# Sheet1.net
KiCad netlist of a schematic drawn in Altium Designer
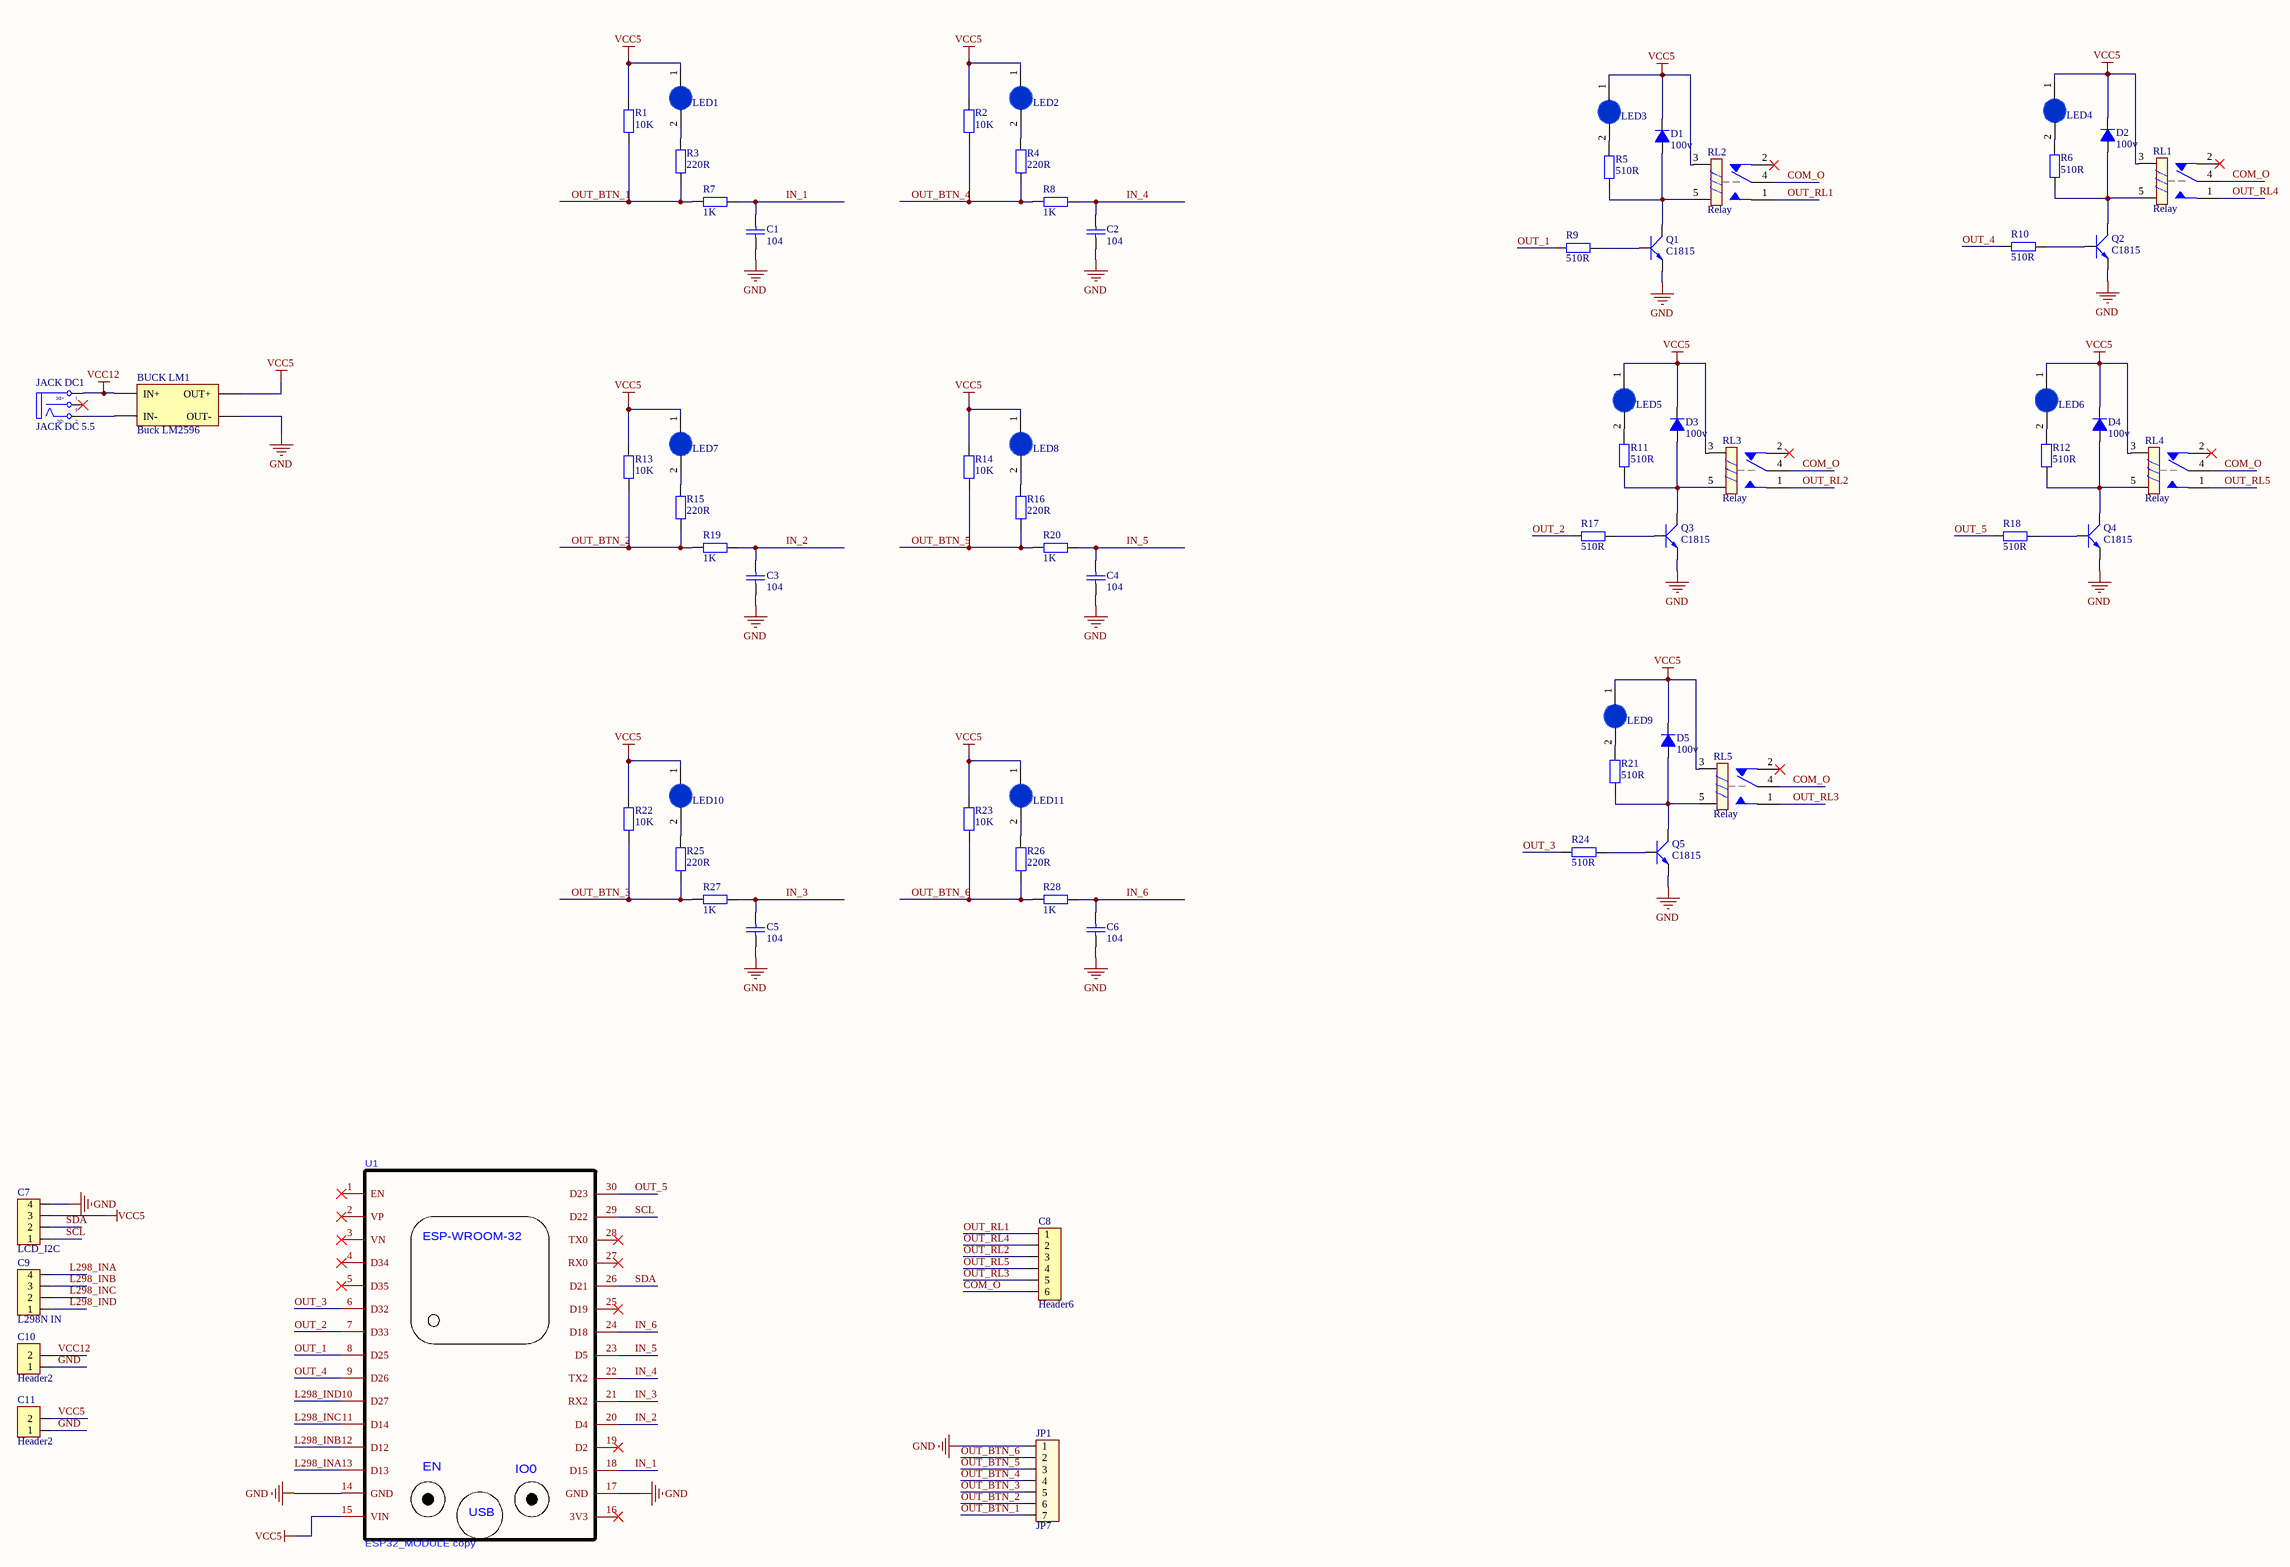
[diagram p0: Sheet1.SchDoc]

(export (version "E")
  (design (tool "Eeschema 10.0.6"))
  (components
    (comp (ref "BUCK LM1")
      (value "Buck LM2596")
      (footprint "BUCK LM2596")
      (libsource (lib "myLib_v1") (part "Buck LM2596"))
    )
    (comp (ref "C1")
      (value "104")
      (footprint "tu gom")
      (description "Cắm")
      (libsource (lib "Altium_Lib_by_KhueNguyenCreator") (part "Tu gom 104 50V"))
    )
    (comp (ref "C2")
      (value "104")
      (footprint "tu gom")
      (description "Cắm")
      (libsource (lib "Altium_Lib_by_KhueNguyenCreator") (part "Tu gom 104 50V"))
    )
    (comp (ref "C3")
      (value "104")
      (footprint "tu gom")
      (description "Cắm")
      (libsource (lib "Altium_Lib_by_KhueNguyenCreator") (part "Tu gom 104 50V"))
    )
    (comp (ref "C4")
      (value "104")
      (footprint "tu gom")
      (description "Cắm")
      (libsource (lib "Altium_Lib_by_KhueNguyenCreator") (part "Tu gom 104 50V"))
    )
    (comp (ref "C5")
      (value "104")
      (footprint "tu gom")
      (description "Cắm")
      (libsource (lib "Altium_Lib_by_KhueNguyenCreator") (part "Tu gom 104 50V"))
    )
    (comp (ref "C6")
      (value "104")
      (footprint "tu gom")
      (description "Cắm")
      (libsource (lib "Altium_Lib_by_KhueNguyenCreator") (part "Tu gom 104 50V"))
    )
    (comp (ref "C7")
      (value "LCD_I2C")
      (footprint "Header4")
      (description "Header IDC, 4 x 1 Pin Vertical 2.54mm Pitch (Non-Boxed, Male)")
      (fields
        (field (name "MANUFACTURER") "Würth Elektronik eiSos GmbH")
        (field (name "PARTNO") "613002143121")
        (field (name "CREATED BY") "Karrer Zheng")
      )
      (libsource (lib "myLib_v1") (part "Header4"))
    )
    (comp (ref "C8")
      (value "Header6")
      (footprint "Header6")
      (description "Header IDC, 6 x 1 Pin Vertical 2.54mm Pitch (Non-Boxed, Male)")
      (fields
        (field (name "MANUFACTURER") "Würth Elektronik eiSos GmbH")
        (field (name "PARTNO") "613002143121")
        (field (name "CREATED BY") "Karrer Zheng")
      )
      (libsource (lib "myLib_v1") (part "Header6"))
    )
    (comp (ref "C9")
      (value "L298N IN")
      (footprint "Header4")
      (description "Header IDC, 4 x 1 Pin Vertical 2.54mm Pitch (Non-Boxed, Male)")
      (fields
        (field (name "MANUFACTURER") "Würth Elektronik eiSos GmbH")
        (field (name "PARTNO") "613002143121")
        (field (name "CREATED BY") "Karrer Zheng")
      )
      (libsource (lib "myLib_v1") (part "Header4"))
    )
    (comp (ref "C10")
      (value "Header2")
      (footprint "Header2")
      (description "Header IDC, 2 x 1 Pin Vertical 2.54mm Pitch (Non-Boxed, Male)")
      (fields
        (field (name "MANUFACTURER") "Würth Elektronik eiSos GmbH")
        (field (name "PARTNO") "613002143121")
        (field (name "CREATED BY") "Karrer Zheng")
      )
      (libsource (lib "myLib_v1") (part "Header2"))
    )
    (comp (ref "C11")
      (value "Header2")
      (footprint "Header2")
      (description "Header IDC, 2 x 1 Pin Vertical 2.54mm Pitch (Non-Boxed, Male)")
      (fields
        (field (name "MANUFACTURER") "Würth Elektronik eiSos GmbH")
        (field (name "PARTNO") "613002143121")
        (field (name "CREATED BY") "Karrer Zheng")
      )
      (libsource (lib "myLib_v1") (part "Header2"))
    )
    (comp (ref "D1")
      (value "100v")
      (footprint "DIODE 0.5A")
      (description "Cắm")
      (libsource (lib "Altium_Lib_by_KhueNguyenCreator") (part "Diode 1N4148"))
    )
    (comp (ref "D2")
      (value "100v")
      (footprint "DIODE 0.5A")
      (description "Cắm")
      (libsource (lib "Altium_Lib_by_KhueNguyenCreator") (part "Diode 1N4148"))
    )
    (comp (ref "D3")
      (value "100v")
      (footprint "DIODE 0.5A")
      (description "Cắm")
      (libsource (lib "Altium_Lib_by_KhueNguyenCreator") (part "Diode 1N4148"))
    )
    (comp (ref "D4")
      (value "100v")
      (footprint "DIODE 0.5A")
      (description "Cắm")
      (libsource (lib "Altium_Lib_by_KhueNguyenCreator") (part "Diode 1N4148"))
    )
    (comp (ref "D5")
      (value "100v")
      (footprint "DIODE 0.5A")
      (description "Cắm")
      (libsource (lib "Altium_Lib_by_KhueNguyenCreator") (part "Diode 1N4148"))
    )
    (comp (ref "JACK DC1")
      (value "JACK DC 5.5")
      (footprint "JACK DC 5.5")
      (libsource (lib "Altium_Lib_by_KhueNguyenCreator") (part "JACK DC 5.5"))
    )
    (comp (ref "JP1")
      (value "JP7")
      (footprint "Header7")
      (description "Connector 7")
      (libsource (lib "myLib_v1") (part "Header7"))
    )
    (comp (ref "LED1")
      (value "LED 3mm")
      (footprint "LED-3MM-BLUE")
      (description "Cắm")
      (libsource (lib "myLib_v1") (part "LED 3mm Xanh Duong"))
    )
    (comp (ref "LED2")
      (value "LED 3mm")
      (footprint "LED-3MM-BLUE")
      (description "Cắm")
      (libsource (lib "myLib_v1") (part "LED 3mm Xanh Duong"))
    )
    (comp (ref "LED3")
      (value "LED 3mm")
      (footprint "LED-3MM-BLUE")
      (description "Cắm")
      (libsource (lib "myLib_v1") (part "LED 3mm Xanh Duong"))
    )
    (comp (ref "LED4")
      (value "LED 3mm")
      (footprint "LED-3MM-BLUE")
      (description "Cắm")
      (libsource (lib "myLib_v1") (part "LED 3mm Xanh Duong"))
    )
    (comp (ref "LED5")
      (value "LED 3mm")
      (footprint "LED-3MM-BLUE")
      (description "Cắm")
      (libsource (lib "myLib_v1") (part "LED 3mm Xanh Duong"))
    )
    (comp (ref "LED6")
      (value "LED 3mm")
      (footprint "LED-3MM-BLUE")
      (description "Cắm")
      (libsource (lib "myLib_v1") (part "LED 3mm Xanh Duong"))
    )
    (comp (ref "LED7")
      (value "LED 3mm")
      (footprint "LED-3MM-BLUE")
      (description "Cắm")
      (libsource (lib "myLib_v1") (part "LED 3mm Xanh Duong"))
    )
    (comp (ref "LED8")
      (value "LED 3mm")
      (footprint "LED-3MM-BLUE")
      (description "Cắm")
      (libsource (lib "myLib_v1") (part "LED 3mm Xanh Duong"))
    )
    (comp (ref "LED9")
      (value "LED 3mm")
      (footprint "LED-3MM-BLUE")
      (description "Cắm")
      (libsource (lib "myLib_v1") (part "LED 3mm Xanh Duong"))
    )
    (comp (ref "LED10")
      (value "LED 3mm")
      (footprint "LED-3MM-BLUE")
      (description "Cắm")
      (libsource (lib "myLib_v1") (part "LED 3mm Xanh Duong"))
    )
    (comp (ref "LED11")
      (value "LED 3mm")
      (footprint "LED-3MM-BLUE")
      (description "Cắm")
      (libsource (lib "myLib_v1") (part "LED 3mm Xanh Duong"))
    )
    (comp (ref "Q1")
      (value "C1815")
      (footprint "C1815_cam")
      (description "NPN 600mW, ECB")
      (libsource (lib "myLib_v1") (part "C1815"))
    )
    (comp (ref "Q2")
      (value "C1815")
      (footprint "C1815_cam")
      (description "NPN 600mW, ECB")
      (libsource (lib "myLib_v1") (part "C1815"))
    )
    (comp (ref "Q3")
      (value "C1815")
      (footprint "C1815_cam")
      (description "NPN 600mW, ECB")
      (libsource (lib "myLib_v1") (part "C1815"))
    )
    (comp (ref "Q4")
      (value "C1815")
      (footprint "C1815_cam")
      (description "NPN 600mW, ECB")
      (libsource (lib "myLib_v1") (part "C1815"))
    )
    (comp (ref "Q5")
      (value "C1815")
      (footprint "C1815_cam")
      (description "NPN 600mW, ECB")
      (libsource (lib "myLib_v1") (part "C1815"))
    )
    (comp (ref "R1")
      (value "10K")
      (footprint "R1/4W")
      (description "Resistor 1/4W")
      (libsource (lib "myLib_v1") (part "R1/4W"))
    )
    (comp (ref "R2")
      (value "10K")
      (footprint "R1/4W")
      (description "Resistor 1/4W")
      (libsource (lib "myLib_v1") (part "R1/4W"))
    )
    (comp (ref "R3")
      (value "220R")
      (footprint "R1/4W")
      (description "Resistor 1/4W")
      (libsource (lib "myLib_v1") (part "R1/4W"))
    )
    (comp (ref "R4")
      (value "220R")
      (footprint "R1/4W")
      (description "Resistor 1/4W")
      (libsource (lib "myLib_v1") (part "R1/4W"))
    )
    (comp (ref "R5")
      (value "510R")
      (footprint "R1/4W")
      (description "Resistor 1/4W")
      (libsource (lib "myLib_v1") (part "R1/4W"))
    )
    (comp (ref "R6")
      (value "510R")
      (footprint "R1/4W")
      (description "Resistor 1/4W")
      (libsource (lib "myLib_v1") (part "R1/4W"))
    )
    (comp (ref "R7")
      (value "1K")
      (footprint "R1/4W")
      (description "Resistor 1/4W")
      (libsource (lib "myLib_v1") (part "R1/4W"))
    )
    (comp (ref "R8")
      (value "1K")
      (footprint "R1/4W")
      (description "Resistor 1/4W")
      (libsource (lib "myLib_v1") (part "R1/4W"))
    )
    (comp (ref "R9")
      (value "510R")
      (footprint "R1/4W")
      (description "Resistor 1/4W")
      (libsource (lib "myLib_v1") (part "R1/4W"))
    )
    (comp (ref "R10")
      (value "510R")
      (footprint "R1/4W")
      (description "Resistor 1/4W")
      (libsource (lib "myLib_v1") (part "R1/4W"))
    )
    (comp (ref "R11")
      (value "510R")
      (footprint "R1/4W")
      (description "Resistor 1/4W")
      (libsource (lib "myLib_v1") (part "R1/4W"))
    )
    (comp (ref "R12")
      (value "510R")
      (footprint "R1/4W")
      (description "Resistor 1/4W")
      (libsource (lib "myLib_v1") (part "R1/4W"))
    )
    (comp (ref "R13")
      (value "10K")
      (footprint "R1/4W")
      (description "Resistor 1/4W")
      (libsource (lib "myLib_v1") (part "R1/4W"))
    )
    (comp (ref "R14")
      (value "10K")
      (footprint "R1/4W")
      (description "Resistor 1/4W")
      (libsource (lib "myLib_v1") (part "R1/4W"))
    )
    (comp (ref "R15")
      (value "220R")
      (footprint "R1/4W")
      (description "Resistor 1/4W")
      (libsource (lib "myLib_v1") (part "R1/4W"))
    )
    (comp (ref "R16")
      (value "220R")
      (footprint "R1/4W")
      (description "Resistor 1/4W")
      (libsource (lib "myLib_v1") (part "R1/4W"))
    )
    (comp (ref "R17")
      (value "510R")
      (footprint "R1/4W")
      (description "Resistor 1/4W")
      (libsource (lib "myLib_v1") (part "R1/4W"))
    )
    (comp (ref "R18")
      (value "510R")
      (footprint "R1/4W")
      (description "Resistor 1/4W")
      (libsource (lib "myLib_v1") (part "R1/4W"))
    )
    (comp (ref "R19")
      (value "1K")
      (footprint "R1/4W")
      (description "Resistor 1/4W")
      (libsource (lib "myLib_v1") (part "R1/4W"))
    )
    (comp (ref "R20")
      (value "1K")
      (footprint "R1/4W")
      (description "Resistor 1/4W")
      (libsource (lib "myLib_v1") (part "R1/4W"))
    )
    (comp (ref "R21")
      (value "510R")
      (footprint "R1/4W")
      (description "Resistor 1/4W")
      (libsource (lib "myLib_v1") (part "R1/4W"))
    )
    (comp (ref "R22")
      (value "10K")
      (footprint "R1/4W")
      (description "Resistor 1/4W")
      (libsource (lib "myLib_v1") (part "R1/4W"))
    )
    (comp (ref "R23")
      (value "10K")
      (footprint "R1/4W")
      (description "Resistor 1/4W")
      (libsource (lib "myLib_v1") (part "R1/4W"))
    )
    (comp (ref "R24")
      (value "510R")
      (footprint "R1/4W")
      (description "Resistor 1/4W")
      (libsource (lib "myLib_v1") (part "R1/4W"))
    )
    (comp (ref "R25")
      (value "220R")
      (footprint "R1/4W")
      (description "Resistor 1/4W")
      (libsource (lib "myLib_v1") (part "R1/4W"))
    )
    (comp (ref "R26")
      (value "220R")
      (footprint "R1/4W")
      (description "Resistor 1/4W")
      (libsource (lib "myLib_v1") (part "R1/4W"))
    )
    (comp (ref "R27")
      (value "1K")
      (footprint "R1/4W")
      (description "Resistor 1/4W")
      (libsource (lib "myLib_v1") (part "R1/4W"))
    )
    (comp (ref "R28")
      (value "1K")
      (footprint "R1/4W")
      (description "Resistor 1/4W")
      (libsource (lib "myLib_v1") (part "R1/4W"))
    )
    (comp (ref "RL1")
      (value "Relay")
      (footprint "RELAY_SRA_05VDC_SL_C")
      (description "Relay 5 Chan")
      (libsource (lib "myLib_v1") (part "RL_SRA-05VDC-SL-C"))
    )
    (comp (ref "RL2")
      (value "Relay")
      (footprint "RELAY_SRA_05VDC_SL_C")
      (description "Relay 5 Chan")
      (libsource (lib "myLib_v1") (part "RL_SRA-05VDC-SL-C"))
    )
    (comp (ref "RL3")
      (value "Relay")
      (footprint "RELAY_SRA_05VDC_SL_C")
      (description "Relay 5 Chan")
      (libsource (lib "myLib_v1") (part "RL_SRA-05VDC-SL-C"))
    )
    (comp (ref "RL4")
      (value "Relay")
      (footprint "RELAY_SRA_05VDC_SL_C")
      (description "Relay 5 Chan")
      (libsource (lib "myLib_v1") (part "RL_SRA-05VDC-SL-C"))
    )
    (comp (ref "RL5")
      (value "Relay")
      (footprint "RELAY_SRA_05VDC_SL_C")
      (description "Relay 5 Chan")
      (libsource (lib "myLib_v1") (part "RL_SRA-05VDC-SL-C"))
    )
    (comp (ref "U1")
      (value "ESP32_MODULE copy")
      (footprint "ESP32-WIFIMODULE-FOOTPRINT")
      (libsource (lib "myLib_v1") (part "ESP32_MODULE copy"))
    )
  )
  (nets
    (net (code "1") (name "/COM_O") (class "Default")
      (node (ref "C8") (pin "6") (pinfunction "6_6") (pintype "passive"))
      (node (ref "RL1") (pin "4") (pinfunction "4_4") (pintype "passive"))
      (node (ref "RL2") (pin "4") (pinfunction "4_4") (pintype "passive"))
      (node (ref "RL3") (pin "4") (pinfunction "4_4") (pintype "passive"))
      (node (ref "RL4") (pin "4") (pinfunction "4_4") (pintype "passive"))
      (node (ref "RL5") (pin "4") (pinfunction "4_4") (pintype "passive"))
    )
    (net (code "2") (name "/IN_1") (class "Default")
      (node (ref "C1") (pin "1") (pinfunction "1_1") (pintype "passive"))
      (node (ref "R7") (pin "1") (pinfunction "1_1") (pintype "passive"))
      (node (ref "U1") (pin "18") (pinfunction "D15_18") (pintype "passive"))
    )
    (net (code "3") (name "/IN_2") (class "Default")
      (node (ref "C3") (pin "1") (pinfunction "1_1") (pintype "passive"))
      (node (ref "R19") (pin "1") (pinfunction "1_1") (pintype "passive"))
      (node (ref "U1") (pin "20") (pinfunction "D4_20") (pintype "passive"))
    )
    (net (code "4") (name "/IN_3") (class "Default")
      (node (ref "C5") (pin "1") (pinfunction "1_1") (pintype "passive"))
      (node (ref "R27") (pin "1") (pinfunction "1_1") (pintype "passive"))
      (node (ref "U1") (pin "21") (pinfunction "RX2_21") (pintype "passive"))
    )
    (net (code "5") (name "/IN_4") (class "Default")
      (node (ref "C2") (pin "1") (pinfunction "1_1") (pintype "passive"))
      (node (ref "R8") (pin "1") (pinfunction "1_1") (pintype "passive"))
      (node (ref "U1") (pin "22") (pinfunction "TX2_22") (pintype "passive"))
    )
    (net (code "6") (name "/IN_5") (class "Default")
      (node (ref "C4") (pin "1") (pinfunction "1_1") (pintype "passive"))
      (node (ref "R20") (pin "1") (pinfunction "1_1") (pintype "passive"))
      (node (ref "U1") (pin "23") (pinfunction "D5_23") (pintype "passive"))
    )
    (net (code "7") (name "/IN_6") (class "Default")
      (node (ref "C6") (pin "1") (pinfunction "1_1") (pintype "passive"))
      (node (ref "R28") (pin "1") (pinfunction "1_1") (pintype "passive"))
      (node (ref "U1") (pin "24") (pinfunction "D18_24") (pintype "passive"))
    )
    (net (code "8") (name "/L298_INA") (class "Default")
      (node (ref "C9") (pin "4") (pinfunction "4_4") (pintype "passive"))
      (node (ref "U1") (pin "13") (pinfunction "D13_13") (pintype "passive"))
    )
    (net (code "9") (name "/L298_INB") (class "Default")
      (node (ref "C9") (pin "3") (pinfunction "3_3") (pintype "passive"))
      (node (ref "U1") (pin "12") (pinfunction "D12_12") (pintype "passive"))
    )
    (net (code "10") (name "/L298_INC") (class "Default")
      (node (ref "C9") (pin "2") (pinfunction "2_2") (pintype "passive"))
      (node (ref "U1") (pin "11") (pinfunction "D14_11") (pintype "passive"))
    )
    (net (code "11") (name "/L298_IND") (class "Default")
      (node (ref "C9") (pin "1") (pinfunction "1_1") (pintype "passive"))
      (node (ref "U1") (pin "10") (pinfunction "D27_10") (pintype "passive"))
    )
    (net (code "12") (name "/OUT_1") (class "Default")
      (node (ref "R9") (pin "1") (pinfunction "1_1") (pintype "passive"))
      (node (ref "U1") (pin "8") (pinfunction "D25_8") (pintype "passive"))
    )
    (net (code "13") (name "/OUT_2") (class "Default")
      (node (ref "R17") (pin "1") (pinfunction "1_1") (pintype "passive"))
      (node (ref "U1") (pin "7") (pinfunction "D33_7") (pintype "passive"))
    )
    (net (code "14") (name "/OUT_3") (class "Default")
      (node (ref "R24") (pin "1") (pinfunction "1_1") (pintype "passive"))
      (node (ref "U1") (pin "6") (pinfunction "D32_6") (pintype "passive"))
    )
    (net (code "15") (name "/OUT_4") (class "Default")
      (node (ref "R10") (pin "1") (pinfunction "1_1") (pintype "passive"))
      (node (ref "U1") (pin "9") (pinfunction "D26_9") (pintype "passive"))
    )
    (net (code "16") (name "/OUT_5") (class "Default")
      (node (ref "R18") (pin "1") (pinfunction "1_1") (pintype "passive"))
      (node (ref "U1") (pin "30") (pinfunction "D23_30") (pintype "passive"))
    )
    (net (code "17") (name "/OUT_BTN_1") (class "Default")
      (node (ref "JP1") (pin "7") (pinfunction "7_7") (pintype "passive"))
      (node (ref "R1") (pin "1") (pinfunction "1_1") (pintype "passive"))
      (node (ref "R3") (pin "1") (pinfunction "1_1") (pintype "passive"))
      (node (ref "R7") (pin "2") (pinfunction "2_2") (pintype "passive"))
    )
    (net (code "18") (name "/OUT_BTN_2") (class "Default")
      (node (ref "JP1") (pin "6") (pinfunction "6_6") (pintype "passive"))
      (node (ref "R13") (pin "1") (pinfunction "1_1") (pintype "passive"))
      (node (ref "R15") (pin "1") (pinfunction "1_1") (pintype "passive"))
      (node (ref "R19") (pin "2") (pinfunction "2_2") (pintype "passive"))
    )
    (net (code "19") (name "/OUT_BTN_3") (class "Default")
      (node (ref "JP1") (pin "5") (pinfunction "5_5") (pintype "passive"))
      (node (ref "R22") (pin "1") (pinfunction "1_1") (pintype "passive"))
      (node (ref "R25") (pin "1") (pinfunction "1_1") (pintype "passive"))
      (node (ref "R27") (pin "2") (pinfunction "2_2") (pintype "passive"))
    )
    (net (code "20") (name "/OUT_BTN_4") (class "Default")
      (node (ref "JP1") (pin "4") (pinfunction "4_4") (pintype "passive"))
      (node (ref "R2") (pin "1") (pinfunction "1_1") (pintype "passive"))
      (node (ref "R4") (pin "1") (pinfunction "1_1") (pintype "passive"))
      (node (ref "R8") (pin "2") (pinfunction "2_2") (pintype "passive"))
    )
    (net (code "21") (name "/OUT_BTN_5") (class "Default")
      (node (ref "JP1") (pin "3") (pinfunction "3_3") (pintype "passive"))
      (node (ref "R14") (pin "1") (pinfunction "1_1") (pintype "passive"))
      (node (ref "R16") (pin "1") (pinfunction "1_1") (pintype "passive"))
      (node (ref "R20") (pin "2") (pinfunction "2_2") (pintype "passive"))
    )
    (net (code "22") (name "/OUT_BTN_6") (class "Default")
      (node (ref "JP1") (pin "2") (pinfunction "2_2") (pintype "passive"))
      (node (ref "R23") (pin "1") (pinfunction "1_1") (pintype "passive"))
      (node (ref "R26") (pin "1") (pinfunction "1_1") (pintype "passive"))
      (node (ref "R28") (pin "2") (pinfunction "2_2") (pintype "passive"))
    )
    (net (code "23") (name "/OUT_RL1") (class "Default")
      (node (ref "C8") (pin "1") (pinfunction "1_1") (pintype "passive"))
      (node (ref "RL2") (pin "1") (pinfunction "1_1") (pintype "passive"))
    )
    (net (code "24") (name "/OUT_RL2") (class "Default")
      (node (ref "C8") (pin "3") (pinfunction "3_3") (pintype "passive"))
      (node (ref "RL3") (pin "1") (pinfunction "1_1") (pintype "passive"))
    )
    (net (code "25") (name "/OUT_RL3") (class "Default")
      (node (ref "C8") (pin "5") (pinfunction "5_5") (pintype "passive"))
      (node (ref "RL5") (pin "1") (pinfunction "1_1") (pintype "passive"))
    )
    (net (code "26") (name "/OUT_RL4") (class "Default")
      (node (ref "C8") (pin "2") (pinfunction "2_2") (pintype "passive"))
      (node (ref "RL1") (pin "1") (pinfunction "1_1") (pintype "passive"))
    )
    (net (code "27") (name "/OUT_RL5") (class "Default")
      (node (ref "C8") (pin "4") (pinfunction "4_4") (pintype "passive"))
      (node (ref "RL4") (pin "1") (pinfunction "1_1") (pintype "passive"))
    )
    (net (code "28") (name "/SCL") (class "Default")
      (node (ref "C7") (pin "1") (pinfunction "1_1") (pintype "passive"))
      (node (ref "U1") (pin "29") (pinfunction "D22_29") (pintype "passive"))
    )
    (net (code "29") (name "/SDA") (class "Default")
      (node (ref "C7") (pin "2") (pinfunction "2_2") (pintype "passive"))
      (node (ref "U1") (pin "26") (pinfunction "D21_26") (pintype "passive"))
    )
    (net (code "30") (name "GND") (class "Default")
      (node (ref "BUCK LM1") (pin "3") (pinfunction "OUT-_3") (pintype "passive"))
      (node (ref "C1") (pin "2") (pinfunction "2_2") (pintype "passive"))
      (node (ref "C10") (pin "1") (pinfunction "1_1") (pintype "passive"))
      (node (ref "C11") (pin "1") (pinfunction "1_1") (pintype "passive"))
      (node (ref "C2") (pin "2") (pinfunction "2_2") (pintype "passive"))
      (node (ref "C3") (pin "2") (pinfunction "2_2") (pintype "passive"))
      (node (ref "C4") (pin "2") (pinfunction "2_2") (pintype "passive"))
      (node (ref "C5") (pin "2") (pinfunction "2_2") (pintype "passive"))
      (node (ref "C6") (pin "2") (pinfunction "2_2") (pintype "passive"))
      (node (ref "C7") (pin "4") (pinfunction "4_4") (pintype "passive"))
      (node (ref "JP1") (pin "1") (pinfunction "1_1") (pintype "passive"))
      (node (ref "Q1") (pin "1") (pinfunction "E_1") (pintype "passive"))
      (node (ref "Q2") (pin "1") (pinfunction "E_1") (pintype "passive"))
      (node (ref "Q3") (pin "1") (pinfunction "E_1") (pintype "passive"))
      (node (ref "Q4") (pin "1") (pinfunction "E_1") (pintype "passive"))
      (node (ref "Q5") (pin "1") (pinfunction "E_1") (pintype "passive"))
      (node (ref "U1") (pin "14") (pinfunction "GND_14") (pintype "passive"))
      (node (ref "U1") (pin "17") (pinfunction "GND_17") (pintype "passive"))
    )
    (net (code "31") (name "Net-(BUCK LM1-IN-)") (class "Default")
      (node (ref "BUCK LM1") (pin "2") (pinfunction "IN-_2") (pintype "passive"))
      (node (ref "JACK DC1") (pin "2") (pinfunction "TN_2") (pintype "passive"))
    )
    (net (code "32") (name "Net-(D1-A)") (class "Default")
      (node (ref "D1") (pin "1") (pinfunction "A_1") (pintype "passive"))
      (node (ref "Q1") (pin "2") (pinfunction "C_2") (pintype "passive"))
      (node (ref "R5") (pin "2") (pinfunction "2_2") (pintype "passive"))
      (node (ref "RL2") (pin "5") (pinfunction "5_5") (pintype "passive"))
    )
    (net (code "33") (name "Net-(D2-A)") (class "Default")
      (node (ref "D2") (pin "1") (pinfunction "A_1") (pintype "passive"))
      (node (ref "Q2") (pin "2") (pinfunction "C_2") (pintype "passive"))
      (node (ref "R6") (pin "2") (pinfunction "2_2") (pintype "passive"))
      (node (ref "RL1") (pin "5") (pinfunction "5_5") (pintype "passive"))
    )
    (net (code "34") (name "Net-(D3-A)") (class "Default")
      (node (ref "D3") (pin "1") (pinfunction "A_1") (pintype "passive"))
      (node (ref "Q3") (pin "2") (pinfunction "C_2") (pintype "passive"))
      (node (ref "R11") (pin "2") (pinfunction "2_2") (pintype "passive"))
      (node (ref "RL3") (pin "5") (pinfunction "5_5") (pintype "passive"))
    )
    (net (code "35") (name "Net-(D4-A)") (class "Default")
      (node (ref "D4") (pin "1") (pinfunction "A_1") (pintype "passive"))
      (node (ref "Q4") (pin "2") (pinfunction "C_2") (pintype "passive"))
      (node (ref "R12") (pin "2") (pinfunction "2_2") (pintype "passive"))
      (node (ref "RL4") (pin "5") (pinfunction "5_5") (pintype "passive"))
    )
    (net (code "36") (name "Net-(D5-A)") (class "Default")
      (node (ref "D5") (pin "1") (pinfunction "A_1") (pintype "passive"))
      (node (ref "Q5") (pin "2") (pinfunction "C_2") (pintype "passive"))
      (node (ref "R21") (pin "2") (pinfunction "2_2") (pintype "passive"))
      (node (ref "RL5") (pin "5") (pinfunction "5_5") (pintype "passive"))
    )
    (net (code "37") (name "Net-(LED1-K)") (class "Default")
      (node (ref "LED1") (pin "2") (pinfunction "K_2") (pintype "passive"))
      (node (ref "R3") (pin "2") (pinfunction "2_2") (pintype "passive"))
    )
    (net (code "38") (name "Net-(LED2-K)") (class "Default")
      (node (ref "LED2") (pin "2") (pinfunction "K_2") (pintype "passive"))
      (node (ref "R4") (pin "2") (pinfunction "2_2") (pintype "passive"))
    )
    (net (code "39") (name "Net-(LED3-K)") (class "Default")
      (node (ref "LED3") (pin "2") (pinfunction "K_2") (pintype "passive"))
      (node (ref "R5") (pin "1") (pinfunction "1_1") (pintype "passive"))
    )
    (net (code "40") (name "Net-(LED4-K)") (class "Default")
      (node (ref "LED4") (pin "2") (pinfunction "K_2") (pintype "passive"))
      (node (ref "R6") (pin "1") (pinfunction "1_1") (pintype "passive"))
    )
    (net (code "41") (name "Net-(LED5-K)") (class "Default")
      (node (ref "LED5") (pin "2") (pinfunction "K_2") (pintype "passive"))
      (node (ref "R11") (pin "1") (pinfunction "1_1") (pintype "passive"))
    )
    (net (code "42") (name "Net-(LED6-K)") (class "Default")
      (node (ref "LED6") (pin "2") (pinfunction "K_2") (pintype "passive"))
      (node (ref "R12") (pin "1") (pinfunction "1_1") (pintype "passive"))
    )
    (net (code "43") (name "Net-(LED7-K)") (class "Default")
      (node (ref "LED7") (pin "2") (pinfunction "K_2") (pintype "passive"))
      (node (ref "R15") (pin "2") (pinfunction "2_2") (pintype "passive"))
    )
    (net (code "44") (name "Net-(LED8-K)") (class "Default")
      (node (ref "LED8") (pin "2") (pinfunction "K_2") (pintype "passive"))
      (node (ref "R16") (pin "2") (pinfunction "2_2") (pintype "passive"))
    )
    (net (code "45") (name "Net-(LED9-K)") (class "Default")
      (node (ref "LED9") (pin "2") (pinfunction "K_2") (pintype "passive"))
      (node (ref "R21") (pin "1") (pinfunction "1_1") (pintype "passive"))
    )
    (net (code "46") (name "Net-(LED10-K)") (class "Default")
      (node (ref "LED10") (pin "2") (pinfunction "K_2") (pintype "passive"))
      (node (ref "R25") (pin "2") (pinfunction "2_2") (pintype "passive"))
    )
    (net (code "47") (name "Net-(LED11-K)") (class "Default")
      (node (ref "LED11") (pin "2") (pinfunction "K_2") (pintype "passive"))
      (node (ref "R26") (pin "2") (pinfunction "2_2") (pintype "passive"))
    )
    (net (code "48") (name "Net-(Q1-B)") (class "Default")
      (node (ref "Q1") (pin "3") (pinfunction "B_3") (pintype "passive"))
      (node (ref "R9") (pin "2") (pinfunction "2_2") (pintype "passive"))
    )
    (net (code "49") (name "Net-(Q2-B)") (class "Default")
      (node (ref "Q2") (pin "3") (pinfunction "B_3") (pintype "passive"))
      (node (ref "R10") (pin "2") (pinfunction "2_2") (pintype "passive"))
    )
    (net (code "50") (name "Net-(Q3-B)") (class "Default")
      (node (ref "Q3") (pin "3") (pinfunction "B_3") (pintype "passive"))
      (node (ref "R17") (pin "2") (pinfunction "2_2") (pintype "passive"))
    )
    (net (code "51") (name "Net-(Q4-B)") (class "Default")
      (node (ref "Q4") (pin "3") (pinfunction "B_3") (pintype "passive"))
      (node (ref "R18") (pin "2") (pinfunction "2_2") (pintype "passive"))
    )
    (net (code "52") (name "Net-(Q5-B)") (class "Default")
      (node (ref "Q5") (pin "3") (pinfunction "B_3") (pintype "passive"))
      (node (ref "R24") (pin "2") (pinfunction "2_2") (pintype "passive"))
    )
    (net (code "53") (name "VCC5") (class "Default")
      (node (ref "BUCK LM1") (pin "4") (pinfunction "OUT+_4") (pintype "passive"))
      (node (ref "C11") (pin "2") (pinfunction "2_2") (pintype "passive"))
      (node (ref "C7") (pin "3") (pinfunction "3_3") (pintype "passive"))
      (node (ref "D1") (pin "2") (pinfunction "K_2") (pintype "passive"))
      (node (ref "D2") (pin "2") (pinfunction "K_2") (pintype "passive"))
      (node (ref "D3") (pin "2") (pinfunction "K_2") (pintype "passive"))
      (node (ref "D4") (pin "2") (pinfunction "K_2") (pintype "passive"))
      (node (ref "D5") (pin "2") (pinfunction "K_2") (pintype "passive"))
      (node (ref "LED1") (pin "1") (pinfunction "A_1") (pintype "passive"))
      (node (ref "LED10") (pin "1") (pinfunction "A_1") (pintype "passive"))
      (node (ref "LED11") (pin "1") (pinfunction "A_1") (pintype "passive"))
      (node (ref "LED2") (pin "1") (pinfunction "A_1") (pintype "passive"))
      (node (ref "LED3") (pin "1") (pinfunction "A_1") (pintype "passive"))
      (node (ref "LED4") (pin "1") (pinfunction "A_1") (pintype "passive"))
      (node (ref "LED5") (pin "1") (pinfunction "A_1") (pintype "passive"))
      (node (ref "LED6") (pin "1") (pinfunction "A_1") (pintype "passive"))
      (node (ref "LED7") (pin "1") (pinfunction "A_1") (pintype "passive"))
      (node (ref "LED8") (pin "1") (pinfunction "A_1") (pintype "passive"))
      (node (ref "LED9") (pin "1") (pinfunction "A_1") (pintype "passive"))
      (node (ref "R1") (pin "2") (pinfunction "2_2") (pintype "passive"))
      (node (ref "R13") (pin "2") (pinfunction "2_2") (pintype "passive"))
      (node (ref "R14") (pin "2") (pinfunction "2_2") (pintype "passive"))
      (node (ref "R2") (pin "2") (pinfunction "2_2") (pintype "passive"))
      (node (ref "R22") (pin "2") (pinfunction "2_2") (pintype "passive"))
      (node (ref "R23") (pin "2") (pinfunction "2_2") (pintype "passive"))
      (node (ref "RL1") (pin "3") (pinfunction "3_3") (pintype "passive"))
      (node (ref "RL2") (pin "3") (pinfunction "3_3") (pintype "passive"))
      (node (ref "RL3") (pin "3") (pinfunction "3_3") (pintype "passive"))
      (node (ref "RL4") (pin "3") (pinfunction "3_3") (pintype "passive"))
      (node (ref "RL5") (pin "3") (pinfunction "3_3") (pintype "passive"))
      (node (ref "U1") (pin "15") (pinfunction "VIN_15") (pintype "passive"))
    )
    (net (code "54") (name "VCC12") (class "Default")
      (node (ref "BUCK LM1") (pin "1") (pinfunction "IN+_1") (pintype "passive"))
      (node (ref "C10") (pin "2") (pinfunction "2_2") (pintype "passive"))
      (node (ref "JACK DC1") (pin "1") (pinfunction "T_1") (pintype "passive"))
    )
    (net (code "55") (name "unconnected-(JACK DC1-S-Pad3)") (class "Default")
      (node (ref "JACK DC1") (pin "3") (pinfunction "S_3") (pintype "power_in+no_connect"))
    )
    (net (code "56") (name "unconnected-(RL1-Pad2)") (class "Default")
      (node (ref "RL1") (pin "2") (pinfunction "2_2") (pintype "passive+no_connect"))
    )
    (net (code "57") (name "unconnected-(RL2-Pad2)") (class "Default")
      (node (ref "RL2") (pin "2") (pinfunction "2_2") (pintype "passive+no_connect"))
    )
    (net (code "58") (name "unconnected-(RL3-Pad2)") (class "Default")
      (node (ref "RL3") (pin "2") (pinfunction "2_2") (pintype "passive+no_connect"))
    )
    (net (code "59") (name "unconnected-(RL4-Pad2)") (class "Default")
      (node (ref "RL4") (pin "2") (pinfunction "2_2") (pintype "passive+no_connect"))
    )
    (net (code "60") (name "unconnected-(RL5-Pad2)") (class "Default")
      (node (ref "RL5") (pin "2") (pinfunction "2_2") (pintype "passive+no_connect"))
    )
    (net (code "61") (name "unconnected-(U1-3V3-Pad16)") (class "Default")
      (node (ref "U1") (pin "16") (pinfunction "3V3_16") (pintype "passive+no_connect"))
    )
    (net (code "62") (name "unconnected-(U1-D2-Pad19)") (class "Default")
      (node (ref "U1") (pin "19") (pinfunction "D2_19") (pintype "passive+no_connect"))
    )
    (net (code "63") (name "unconnected-(U1-D19-Pad25)") (class "Default")
      (node (ref "U1") (pin "25") (pinfunction "D19_25") (pintype "passive+no_connect"))
    )
    (net (code "64") (name "unconnected-(U1-D34-Pad4)") (class "Default")
      (node (ref "U1") (pin "4") (pinfunction "D34_4") (pintype "passive+no_connect"))
    )
    (net (code "65") (name "unconnected-(U1-D35-Pad5)") (class "Default")
      (node (ref "U1") (pin "5") (pinfunction "D35_5") (pintype "passive+no_connect"))
    )
    (net (code "66") (name "unconnected-(U1-EN-Pad1)") (class "Default")
      (node (ref "U1") (pin "1") (pinfunction "EN_1") (pintype "passive+no_connect"))
    )
    (net (code "67") (name "unconnected-(U1-RX0-Pad27)") (class "Default")
      (node (ref "U1") (pin "27") (pinfunction "RX0_27") (pintype "passive+no_connect"))
    )
    (net (code "68") (name "unconnected-(U1-TX0-Pad28)") (class "Default")
      (node (ref "U1") (pin "28") (pinfunction "TX0_28") (pintype "passive+no_connect"))
    )
    (net (code "69") (name "unconnected-(U1-VN-Pad3)") (class "Default")
      (node (ref "U1") (pin "3") (pinfunction "VN_3") (pintype "passive+no_connect"))
    )
    (net (code "70") (name "unconnected-(U1-VP-Pad2)") (class "Default")
      (node (ref "U1") (pin "2") (pinfunction "VP_2") (pintype "passive+no_connect"))
    )
  )
)
